# ASD2003.net
KiCad netlist of a schematic drawn in EAGLE
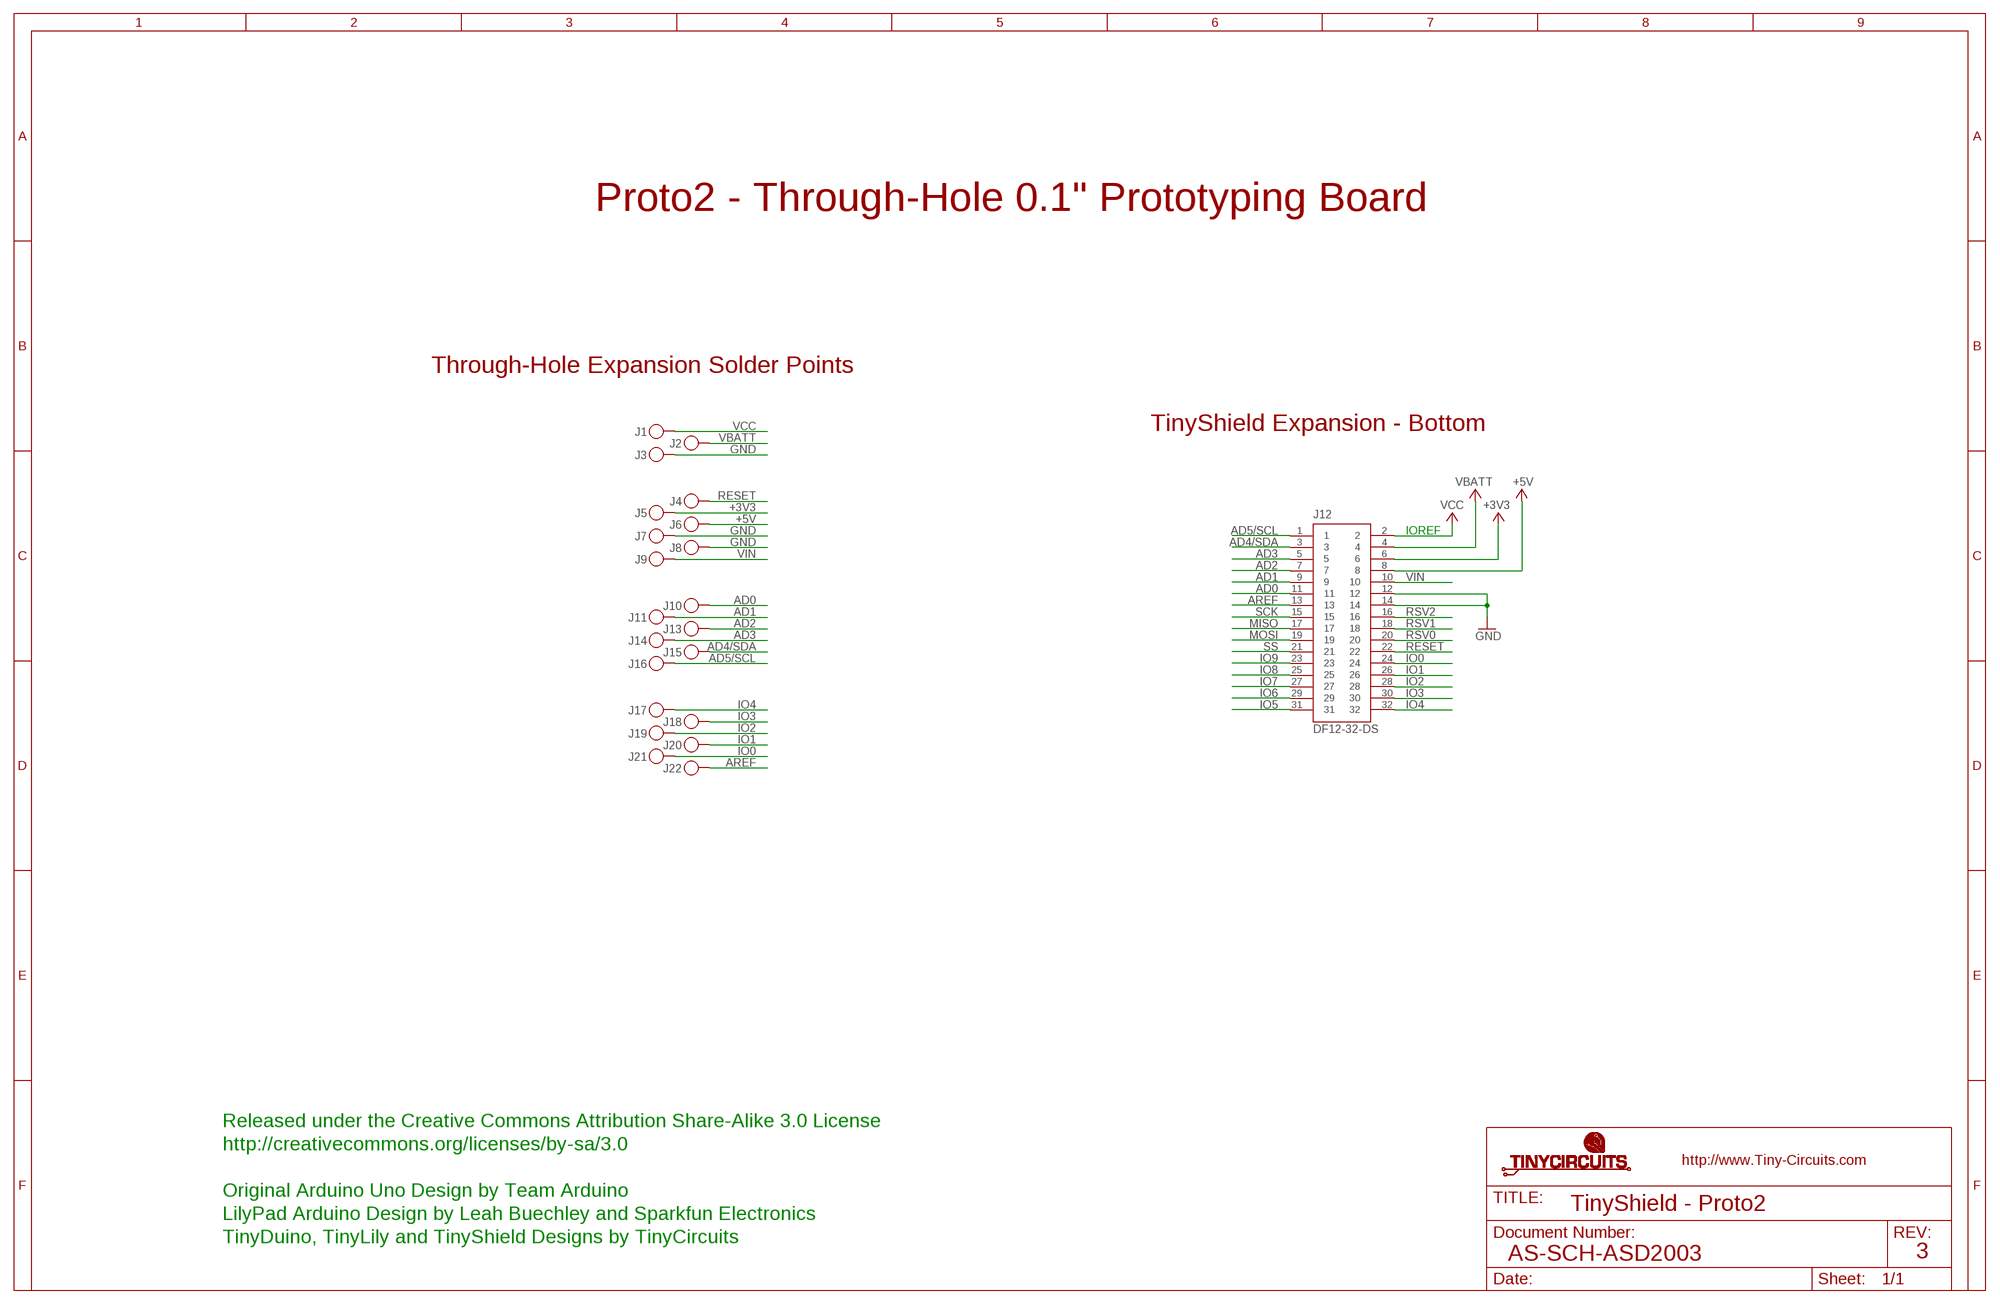
[diagram p0: schematic, sheet 1]

(export (version "E")
  (design (tool "Eeschema 10.0.6"))
  (components
    (comp (ref "J1")
      (value "PIN_1X.1\"1")
      (footprint "eagle-import:1X.1__2")
      (fields (field (name "PARTNO") "COPPER"))
      (libsource (lib "eagle-import") (part "PIN_1X.1{dblquote}1"))
    )
    (comp (ref "J2")
      (value "PIN_1X.1\"1")
      (footprint "eagle-import:1X.1__2")
      (fields (field (name "PARTNO") "COPPER"))
      (libsource (lib "eagle-import") (part "PIN_1X.1{dblquote}1"))
    )
    (comp (ref "J3")
      (value "PIN_1X.1\"1")
      (footprint "eagle-import:1X.1__2")
      (fields (field (name "PARTNO") "COPPER"))
      (libsource (lib "eagle-import") (part "PIN_1X.1{dblquote}1"))
    )
    (comp (ref "J4")
      (value "PIN_1X.1\"1")
      (footprint "eagle-import:1X.1__2")
      (fields (field (name "PARTNO") "COPPER"))
      (libsource (lib "eagle-import") (part "PIN_1X.1{dblquote}1"))
    )
    (comp (ref "J5")
      (value "PIN_1X.1\"1")
      (footprint "eagle-import:1X.1__2")
      (fields (field (name "PARTNO") "COPPER"))
      (libsource (lib "eagle-import") (part "PIN_1X.1{dblquote}1"))
    )
    (comp (ref "J6")
      (value "PIN_1X.1\"1")
      (footprint "eagle-import:1X.1__2")
      (fields (field (name "PARTNO") "COPPER"))
      (libsource (lib "eagle-import") (part "PIN_1X.1{dblquote}1"))
    )
    (comp (ref "J7")
      (value "PIN_1X.1\"1")
      (footprint "eagle-import:1X.1__2")
      (fields (field (name "PARTNO") "COPPER"))
      (libsource (lib "eagle-import") (part "PIN_1X.1{dblquote}1"))
    )
    (comp (ref "J8")
      (value "PIN_1X.1\"1")
      (footprint "eagle-import:1X.1__2")
      (fields (field (name "PARTNO") "COPPER"))
      (libsource (lib "eagle-import") (part "PIN_1X.1{dblquote}1"))
    )
    (comp (ref "J9")
      (value "PIN_1X.1\"1")
      (footprint "eagle-import:1X.1__2")
      (fields (field (name "PARTNO") "COPPER"))
      (libsource (lib "eagle-import") (part "PIN_1X.1{dblquote}1"))
    )
    (comp (ref "J10")
      (value "PIN_1X.1\"1")
      (footprint "eagle-import:1X.1__2")
      (fields (field (name "PARTNO") "COPPER"))
      (libsource (lib "eagle-import") (part "PIN_1X.1{dblquote}1"))
    )
    (comp (ref "J11")
      (value "PIN_1X.1\"1")
      (footprint "eagle-import:1X.1__2")
      (fields (field (name "PARTNO") "COPPER"))
      (libsource (lib "eagle-import") (part "PIN_1X.1{dblquote}1"))
    )
    (comp (ref "J12")
      (value "DF12-32-DS")
      (footprint "eagle-import:DF12-32-DS")
      (fields (field (name "PARTNO") "AS-ITM-00012") (field (name "PARTNO_1") "AS-ITM-00012"))
      (libsource (lib "eagle-import") (part "AS-ITM-00012"))
    )
    (comp (ref "J13")
      (value "PIN_1X.1\"1")
      (footprint "eagle-import:1X.1__2")
      (fields (field (name "PARTNO") "COPPER"))
      (libsource (lib "eagle-import") (part "PIN_1X.1{dblquote}1"))
    )
    (comp (ref "J14")
      (value "PIN_1X.1\"1")
      (footprint "eagle-import:1X.1__2")
      (fields (field (name "PARTNO") "COPPER"))
      (libsource (lib "eagle-import") (part "PIN_1X.1{dblquote}1"))
    )
    (comp (ref "J15")
      (value "PIN_1X.1\"1")
      (footprint "eagle-import:1X.1__2")
      (fields (field (name "PARTNO") "COPPER"))
      (libsource (lib "eagle-import") (part "PIN_1X.1{dblquote}1"))
    )
    (comp (ref "J16")
      (value "PIN_1X.1\"1")
      (footprint "eagle-import:1X.1__2")
      (fields (field (name "PARTNO") "COPPER"))
      (libsource (lib "eagle-import") (part "PIN_1X.1{dblquote}1"))
    )
    (comp (ref "J17")
      (value "PIN_1X.1\"1")
      (footprint "eagle-import:1X.1__2")
      (fields (field (name "PARTNO") "COPPER"))
      (libsource (lib "eagle-import") (part "PIN_1X.1{dblquote}1"))
    )
    (comp (ref "J18")
      (value "PIN_1X.1\"1")
      (footprint "eagle-import:1X.1__2")
      (fields (field (name "PARTNO") "COPPER"))
      (libsource (lib "eagle-import") (part "PIN_1X.1{dblquote}1"))
    )
    (comp (ref "J19")
      (value "PIN_1X.1\"1")
      (footprint "eagle-import:1X.1__2")
      (fields (field (name "PARTNO") "COPPER"))
      (libsource (lib "eagle-import") (part "PIN_1X.1{dblquote}1"))
    )
    (comp (ref "J20")
      (value "PIN_1X.1\"1")
      (footprint "eagle-import:1X.1__2")
      (fields (field (name "PARTNO") "COPPER"))
      (libsource (lib "eagle-import") (part "PIN_1X.1{dblquote}1"))
    )
    (comp (ref "J21")
      (value "PIN_1X.1\"1")
      (footprint "eagle-import:1X.1__2")
      (fields (field (name "PARTNO") "COPPER"))
      (libsource (lib "eagle-import") (part "PIN_1X.1{dblquote}1"))
    )
    (comp (ref "J22")
      (value "PIN_1X.1\"1")
      (footprint "eagle-import:1X.1__2")
      (fields (field (name "PARTNO") "COPPER"))
      (libsource (lib "eagle-import") (part "PIN_1X.1{dblquote}1"))
    )
  )
  (nets
    (net (code "1") (name "+3V3") (class "Default")
      (node (ref "J12") (pin "6") (pinfunction "6_6") (pintype "bidirectional"))
      (node (ref "J5") (pin "1") (pinfunction "1_1") (pintype "bidirectional"))
    )
    (net (code "2") (name "+5V") (class "Default")
      (node (ref "J12") (pin "8") (pinfunction "8_8") (pintype "bidirectional"))
      (node (ref "J6") (pin "1") (pinfunction "1_1") (pintype "bidirectional"))
    )
    (net (code "3") (name "/AD0") (class "Default")
      (node (ref "J10") (pin "1") (pinfunction "1_1") (pintype "bidirectional"))
      (node (ref "J12") (pin "11") (pinfunction "11_11") (pintype "bidirectional"))
    )
    (net (code "4") (name "/AD1") (class "Default")
      (node (ref "J11") (pin "1") (pinfunction "1_1") (pintype "bidirectional"))
      (node (ref "J12") (pin "9") (pinfunction "9_9") (pintype "bidirectional"))
    )
    (net (code "5") (name "/AD2") (class "Default")
      (node (ref "J12") (pin "7") (pinfunction "7_7") (pintype "bidirectional"))
      (node (ref "J13") (pin "1") (pinfunction "1_1") (pintype "bidirectional"))
    )
    (net (code "6") (name "/AD3") (class "Default")
      (node (ref "J12") (pin "5") (pinfunction "5_5") (pintype "bidirectional"))
      (node (ref "J14") (pin "1") (pinfunction "1_1") (pintype "bidirectional"))
    )
    (net (code "7") (name "/AD4{slash}SDA") (class "Default")
      (node (ref "J12") (pin "3") (pinfunction "3_3") (pintype "bidirectional"))
      (node (ref "J15") (pin "1") (pinfunction "1_1") (pintype "bidirectional"))
    )
    (net (code "8") (name "/AD5{slash}SCL") (class "Default")
      (node (ref "J12") (pin "1") (pinfunction "1_1") (pintype "bidirectional"))
      (node (ref "J16") (pin "1") (pinfunction "1_1") (pintype "bidirectional"))
    )
    (net (code "9") (name "/AREF") (class "Default")
      (node (ref "J12") (pin "13") (pinfunction "13_13") (pintype "bidirectional"))
      (node (ref "J22") (pin "1") (pinfunction "1_1") (pintype "bidirectional"))
    )
    (net (code "10") (name "/IO0") (class "Default")
      (node (ref "J12") (pin "24") (pinfunction "24_24") (pintype "bidirectional"))
      (node (ref "J21") (pin "1") (pinfunction "1_1") (pintype "bidirectional"))
    )
    (net (code "11") (name "/IO1") (class "Default")
      (node (ref "J12") (pin "26") (pinfunction "26_26") (pintype "bidirectional"))
      (node (ref "J20") (pin "1") (pinfunction "1_1") (pintype "bidirectional"))
    )
    (net (code "12") (name "/IO2") (class "Default")
      (node (ref "J12") (pin "28") (pinfunction "28_28") (pintype "bidirectional"))
      (node (ref "J19") (pin "1") (pinfunction "1_1") (pintype "bidirectional"))
    )
    (net (code "13") (name "/IO3") (class "Default")
      (node (ref "J12") (pin "30") (pinfunction "30_30") (pintype "bidirectional"))
      (node (ref "J18") (pin "1") (pinfunction "1_1") (pintype "bidirectional"))
    )
    (net (code "14") (name "/IO4") (class "Default")
      (node (ref "J12") (pin "32") (pinfunction "32_32") (pintype "bidirectional"))
      (node (ref "J17") (pin "1") (pinfunction "1_1") (pintype "bidirectional"))
    )
    (net (code "15") (name "/IO5") (class "Default")
      (node (ref "J12") (pin "31") (pinfunction "31_31") (pintype "bidirectional"))
    )
    (net (code "16") (name "/IO6") (class "Default")
      (node (ref "J12") (pin "29") (pinfunction "29_29") (pintype "bidirectional"))
    )
    (net (code "17") (name "/IO7") (class "Default")
      (node (ref "J12") (pin "27") (pinfunction "27_27") (pintype "bidirectional"))
    )
    (net (code "18") (name "/IO8") (class "Default")
      (node (ref "J12") (pin "25") (pinfunction "25_25") (pintype "bidirectional"))
    )
    (net (code "19") (name "/IO9") (class "Default")
      (node (ref "J12") (pin "23") (pinfunction "23_23") (pintype "bidirectional"))
    )
    (net (code "20") (name "/MISO") (class "Default")
      (node (ref "J12") (pin "17") (pinfunction "17_17") (pintype "bidirectional"))
    )
    (net (code "21") (name "/MOSI") (class "Default")
      (node (ref "J12") (pin "19") (pinfunction "19_19") (pintype "bidirectional"))
    )
    (net (code "22") (name "/RESET") (class "Default")
      (node (ref "J12") (pin "22") (pinfunction "22_22") (pintype "bidirectional"))
      (node (ref "J4") (pin "1") (pinfunction "1_1") (pintype "bidirectional"))
    )
    (net (code "23") (name "/RSV0") (class "Default")
      (node (ref "J12") (pin "20") (pinfunction "20_20") (pintype "bidirectional"))
    )
    (net (code "24") (name "/RSV1") (class "Default")
      (node (ref "J12") (pin "18") (pinfunction "18_18") (pintype "bidirectional"))
    )
    (net (code "25") (name "/RSV2") (class "Default")
      (node (ref "J12") (pin "16") (pinfunction "16_16") (pintype "bidirectional"))
    )
    (net (code "26") (name "/SCK") (class "Default")
      (node (ref "J12") (pin "15") (pinfunction "15_15") (pintype "bidirectional"))
    )
    (net (code "27") (name "/SS") (class "Default")
      (node (ref "J12") (pin "21") (pinfunction "21_21") (pintype "bidirectional"))
    )
    (net (code "28") (name "/VIN") (class "Default")
      (node (ref "J12") (pin "10") (pinfunction "10_10") (pintype "bidirectional"))
      (node (ref "J9") (pin "1") (pinfunction "1_1") (pintype "bidirectional"))
    )
    (net (code "29") (name "GND") (class "Default")
      (node (ref "J12") (pin "12") (pinfunction "12_12") (pintype "bidirectional"))
      (node (ref "J12") (pin "14") (pinfunction "14_14") (pintype "bidirectional"))
      (node (ref "J3") (pin "1") (pinfunction "1_1") (pintype "bidirectional"))
      (node (ref "J7") (pin "1") (pinfunction "1_1") (pintype "bidirectional"))
      (node (ref "J8") (pin "1") (pinfunction "1_1") (pintype "bidirectional"))
    )
    (net (code "30") (name "VBATT") (class "Default")
      (node (ref "J12") (pin "4") (pinfunction "4_4") (pintype "bidirectional"))
      (node (ref "J2") (pin "1") (pinfunction "1_1") (pintype "bidirectional"))
    )
    (net (code "31") (name "VCC") (class "Default")
      (node (ref "J1") (pin "1") (pinfunction "1_1") (pintype "bidirectional"))
      (node (ref "J12") (pin "2") (pinfunction "2_2") (pintype "bidirectional"))
    )
  )
)
